# zerocam2S_revE.net
KiCad netlist of a schematic drawn in EAGLE
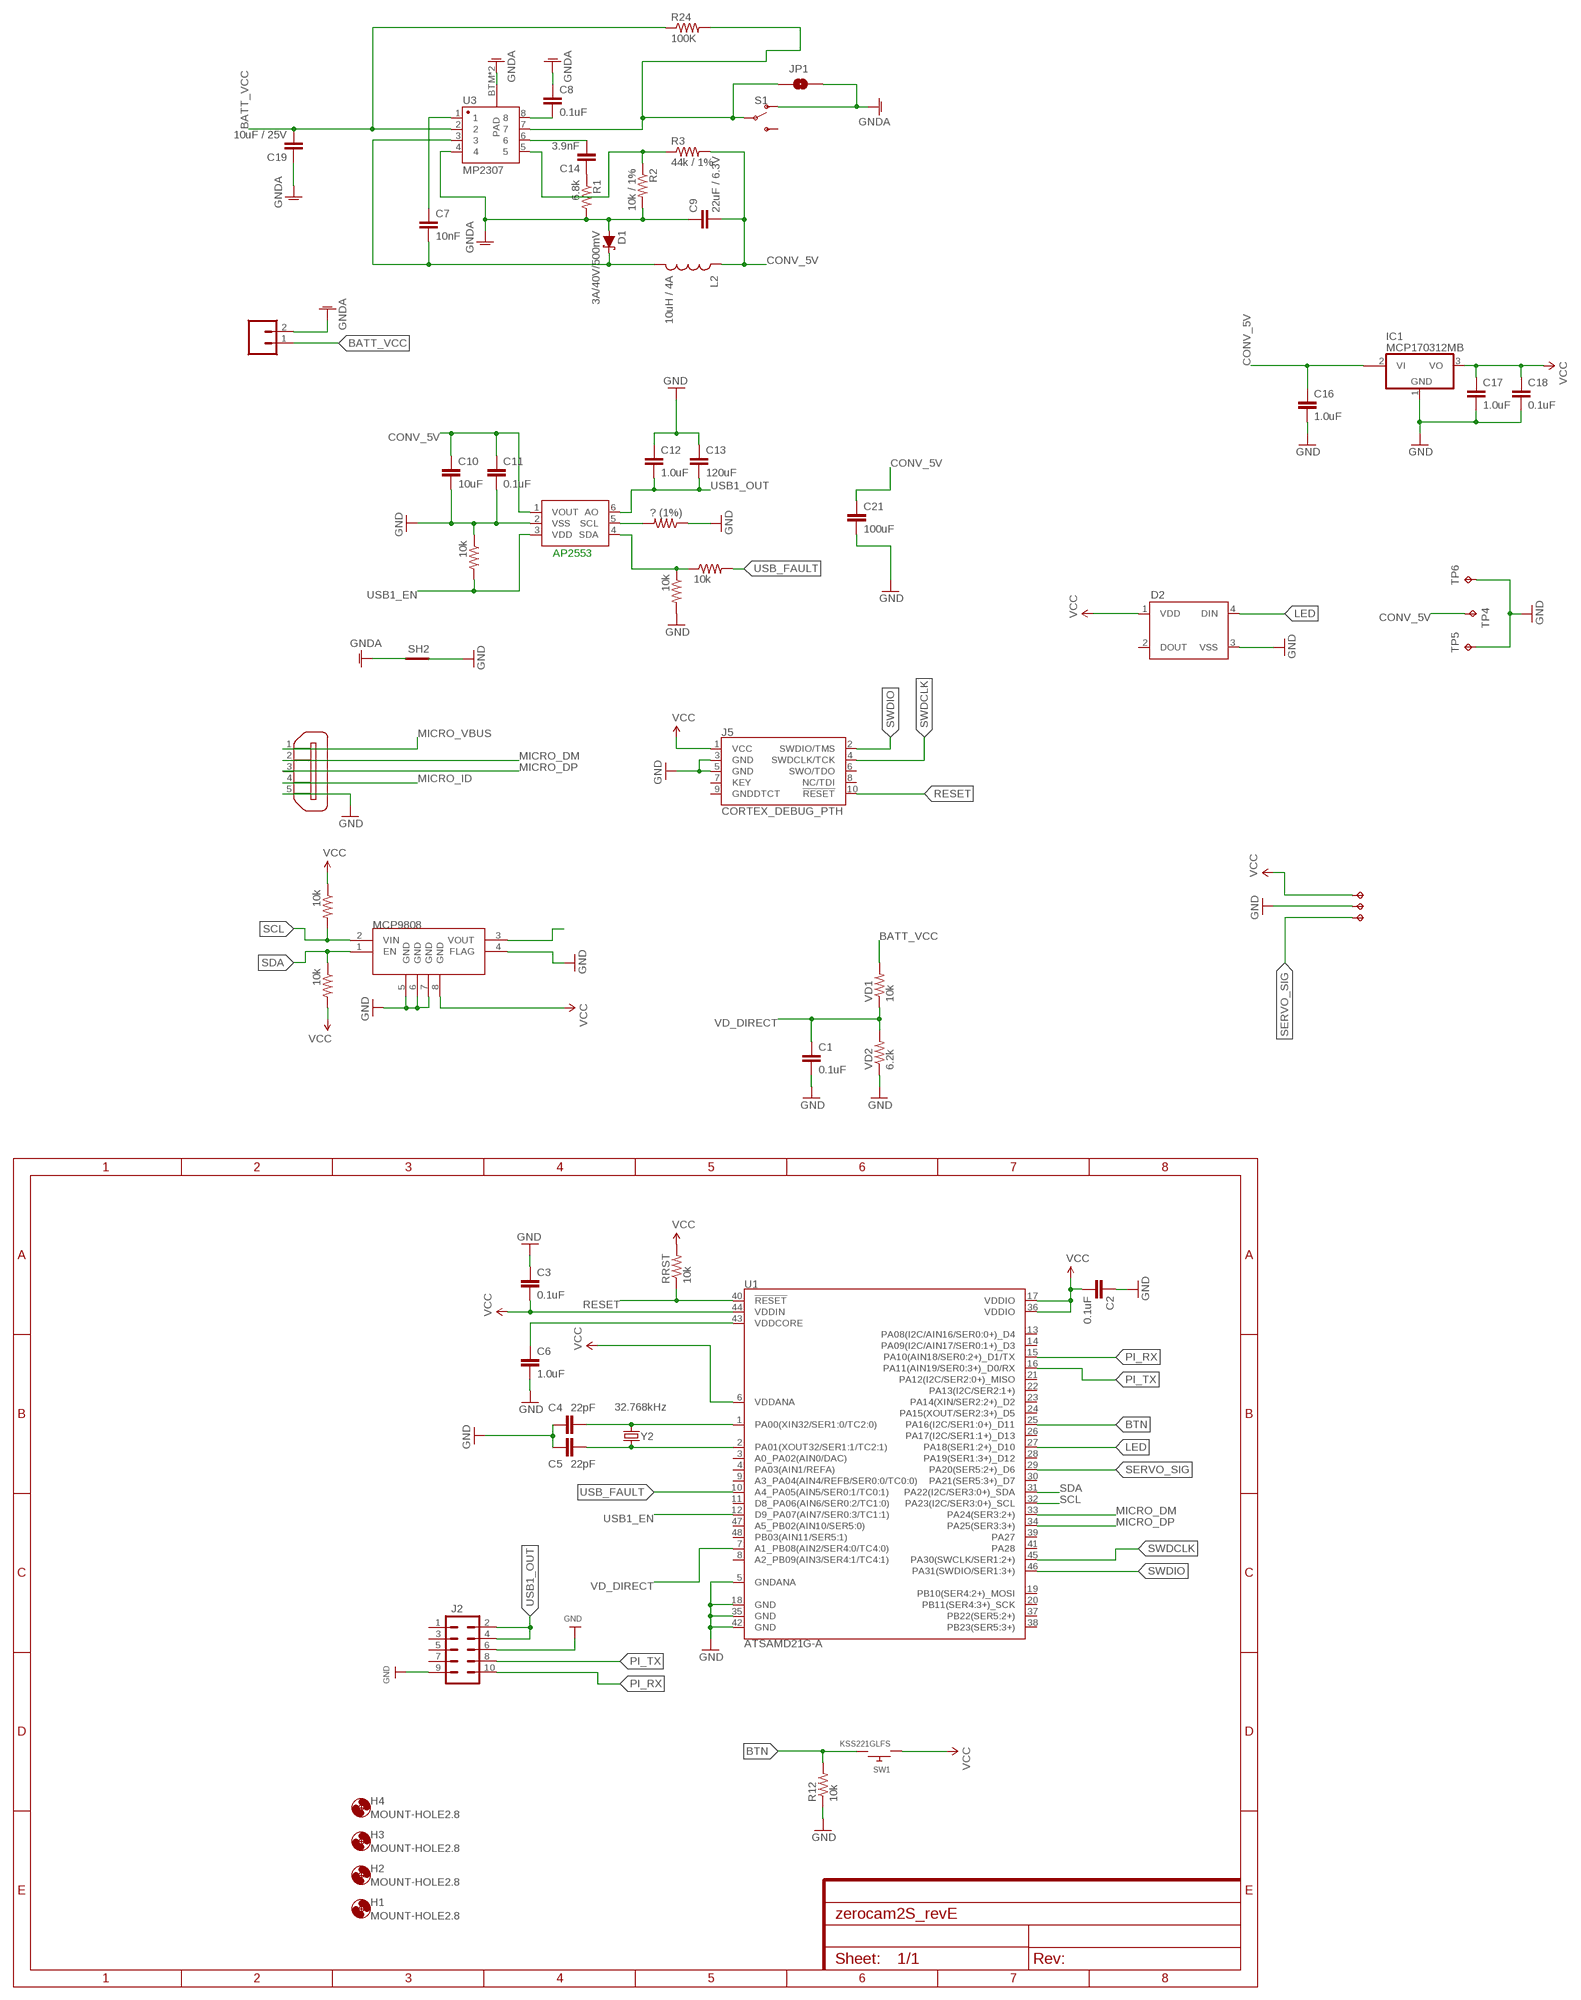
[diagram p0: schematic, sheet 1]

(export (version "E")
  (design (tool "Eeschema 10.0.6"))
  (components
    (comp (ref "AP2553")
      (value "MCP4725")
      (footprint "eagle-import:SOT23-6")
      (libsource (lib "eagle-import") (part "MCP4725SOT-23"))
    )
    (comp (ref "C1")
      (value "0.1uF")
      (footprint "eagle-import:0805")
      (libsource (lib "eagle-import") (part "CAP0805"))
    )
    (comp (ref "C2")
      (value "0.1uF")
      (footprint "eagle-import:0805")
      (libsource (lib "eagle-import") (part "1.0UF-0805-25V-10%"))
    )
    (comp (ref "C3")
      (value "0.1uF")
      (footprint "eagle-import:0805")
      (libsource (lib "eagle-import") (part "1.0UF-0805-25V-10%"))
    )
    (comp (ref "C4")
      (value "22pF")
      (footprint "eagle-import:0805")
      (libsource (lib "eagle-import") (part "SparkFun-Passives_CAP0805"))
    )
    (comp (ref "C5")
      (value "22pF")
      (footprint "eagle-import:0805")
      (libsource (lib "eagle-import") (part "SparkFun-Passives_CAP0805"))
    )
    (comp (ref "C6")
      (value "1.0uF")
      (footprint "eagle-import:0805")
      (libsource (lib "eagle-import") (part "1.0UF-0805-25V-10%"))
    )
    (comp (ref "C7")
      (value "10nF")
      (footprint "eagle-import:0805")
      (libsource (lib "eagle-import") (part "CAP0805"))
    )
    (comp (ref "C8")
      (value "0.1uF")
      (footprint "eagle-import:1206")
      (libsource (lib "eagle-import") (part "CAP1206"))
    )
    (comp (ref "C9")
      (value "22uF / 6.3V")
      (footprint "eagle-import:1210")
      (libsource (lib "eagle-import") (part "CAP1210"))
    )
    (comp (ref "C10")
      (value "10uF")
      (footprint "eagle-import:0805")
      (libsource (lib "eagle-import") (part "1.0UF-0805-25V-10%"))
    )
    (comp (ref "C11")
      (value "0.1uF")
      (footprint "eagle-import:0805")
      (libsource (lib "eagle-import") (part "1.0UF-0805-25V-10%"))
    )
    (comp (ref "C12")
      (value "1.0uF")
      (footprint "eagle-import:1206")
      (libsource (lib "eagle-import") (part "1.0UF-1206-50V-10%"))
    )
    (comp (ref "C13")
      (value "120uF")
      (footprint "eagle-import:1206")
      (libsource (lib "eagle-import") (part "1.0UF-1206-50V-10%"))
    )
    (comp (ref "C14")
      (value "3.9nF")
      (footprint "eagle-import:1206")
      (libsource (lib "eagle-import") (part "CAP1206"))
    )
    (comp (ref "C16")
      (value "1.0uF")
      (footprint "eagle-import:0805")
      (libsource (lib "eagle-import") (part "1.0UF-0805-25V-10%"))
    )
    (comp (ref "C17")
      (value "1.0uF")
      (footprint "eagle-import:1206")
      (libsource (lib "eagle-import") (part "1.0UF-1206-50V-10%"))
    )
    (comp (ref "C18")
      (value "0.1uF")
      (footprint "eagle-import:0805")
      (libsource (lib "eagle-import") (part "1.0UF-0805-25V-10%"))
    )
    (comp (ref "C19")
      (value "10uF / 25V")
      (footprint "eagle-import:1210")
      (libsource (lib "eagle-import") (part "CAP1210"))
    )
    (comp (ref "C21")
      (value "100uF")
      (footprint "eagle-import:1210")
      (libsource (lib "eagle-import") (part "10UF-1210-50V-20%"))
    )
    (comp (ref "D1")
      (value "3A/40V/500mV")
      (footprint "eagle-import:SMA-DIODE")
      (libsource (lib "eagle-import") (part "DIODE-SCHOTTKY-B340A"))
    )
    (comp (ref "D2")
      (value "WS2812B")
      (footprint "eagle-import:WS2812B")
      (libsource (lib "eagle-import") (part "WS2812B"))
    )
    (comp (ref "H1")
      (value "MOUNT-HOLE2.8")
      (footprint "eagle-import:2,8")
      (libsource (lib "eagle-import") (part "MOUNT-HOLE2.8"))
    )
    (comp (ref "H2")
      (value "MOUNT-HOLE2.8")
      (footprint "eagle-import:2,8")
      (libsource (lib "eagle-import") (part "MOUNT-HOLE2.8"))
    )
    (comp (ref "H3")
      (value "MOUNT-HOLE2.8")
      (footprint "eagle-import:2,8")
      (libsource (lib "eagle-import") (part "MOUNT-HOLE2.8"))
    )
    (comp (ref "H4")
      (value "MOUNT-HOLE2.8")
      (footprint "eagle-import:2,8")
      (libsource (lib "eagle-import") (part "MOUNT-HOLE2.8"))
    )
    (comp (ref "IC1")
      (value "MCP170312MB")
      (footprint "eagle-import:SOT89")
      (libsource (lib "eagle-import") (part "MCP1703MB12"))
    )
    (comp (ref "J1")
      (value "CONN_023.5MM-NO_SILK")
      (footprint "eagle-import:SCREWTERMINAL-3.5MM-2-NS")
      (libsource (lib "eagle-import") (part "CONN_023.5MM-NO_SILK"))
    )
    (comp (ref "J2")
      (value "M05X2PTH")
      (footprint "eagle-import:AVR_ICSP")
      (libsource (lib "eagle-import") (part "M05X2PTH"))
    )
    (comp (ref "J5")
      (value "CORTEX_DEBUG_PTH")
      (footprint "eagle-import:2X5-PTH-1.27MM")
      (libsource (lib "eagle-import") (part "CORTEX_DEBUG_PTH"))
    )
    (comp (ref "JP1")
      (value "JUMPER-SMT_2_NO_NO-SILK")
      (footprint "eagle-import:SMT-JUMPER_2_NO_NO-SILK")
      (libsource (lib "eagle-import") (part "JUMPER-SMT_2_NO_NO-SILK"))
    )
    (comp (ref "L2")
      (value "10uH / 4A")
      (footprint "eagle-import:SRU1038")
      (libsource (lib "eagle-import") (part "INDUCTORSRU1038"))
    )
    (comp (ref "MCP9808")
      (value "V_REG_MIC5216")
      (footprint "eagle-import:MSOP8")
      (libsource (lib "eagle-import") (part "V_REG_MIC5216"))
    )
    (comp (ref "R1")
      (value "6.8k")
      (footprint "eagle-import:1206")
      (libsource (lib "eagle-import") (part "SparkFun-Resistors_RESISTOR1206"))
    )
    (comp (ref "R2")
      (value "10k / 1%")
      (footprint "eagle-import:1206")
      (libsource (lib "eagle-import") (part "SparkFun-Resistors_RESISTOR1206"))
    )
    (comp (ref "R3")
      (value "44k / 1%")
      (footprint "eagle-import:1206")
      (libsource (lib "eagle-import") (part "SparkFun-Resistors_RESISTOR1206"))
    )
    (comp (ref "R12")
      (value "10k")
      (footprint "eagle-import:0805")
      (libsource (lib "eagle-import") (part "RESISTOR0805-RES"))
    )
    (comp (ref "R24")
      (value "100K")
      (footprint "eagle-import:1206")
      (libsource (lib "eagle-import") (part "SparkFun-Resistors_RESISTOR1206"))
    )
    (comp (ref "RRST")
      (value "10k")
      (footprint "eagle-import:0805")
      (libsource (lib "eagle-import") (part "RESISTOR0805-RES"))
    )
    (comp (ref "R_I2C_1")
      (value "10k")
      (footprint "eagle-import:0805")
      (libsource (lib "eagle-import") (part "RESISTOR0805-RES"))
    )
    (comp (ref "R_I2C_2")
      (value "10k")
      (footprint "eagle-import:0805")
      (libsource (lib "eagle-import") (part "RESISTOR0805-RES"))
    )
    (comp (ref "R_MOSFET_USB1")
      (value "? (1%)")
      (footprint "eagle-import:0805")
      (libsource (lib "eagle-import") (part "RESISTOR0805-RES"))
    )
    (comp (ref "R_MOSFET_USB2")
      (value "10k")
      (footprint "eagle-import:0805")
      (libsource (lib "eagle-import") (part "RESISTOR0805-RES"))
    )
    (comp (ref "R_MOSFET_USB3")
      (value "10k")
      (footprint "eagle-import:0805")
      (libsource (lib "eagle-import") (part "RESISTOR0805-RES"))
    )
    (comp (ref "R_MOSFET_USB4")
      (value "10k")
      (footprint "eagle-import:0805")
      (libsource (lib "eagle-import") (part "RESISTOR0805-RES"))
    )
    (comp (ref "S1")
      (value "SWITCH-SPDT-SMD-RIGHT-ANGLE")
      (footprint "eagle-import:SWITCH_SPST_SMD_A")
      (libsource (lib "eagle-import") (part "SWITCH-SPDT-SMD-RIGHT-ANGLE"))
    )
    (comp (ref "SH2")
      (value "SHORT-HT5")
      (footprint "eagle-import:SHORT_TOP-50")
      (libsource (lib "eagle-import") (part "SHORT-HT5"))
    )
    (comp (ref "SW1")
      (value "KSS221GLFS")
      (footprint "eagle-import:BTN_CK_KSS")
      (libsource (lib "eagle-import") (part "SWITCH_PUSHBUTTONC&K_KSS"))
    )
    (comp (ref "TP1")
      (value "TPPAD1-13Y")
      (footprint "eagle-import:P1-13Y")
      (libsource (lib "eagle-import") (part "TPPAD1-13Y"))
    )
    (comp (ref "TP2")
      (value "TPPAD1-13Y")
      (footprint "eagle-import:P1-13Y")
      (libsource (lib "eagle-import") (part "TPPAD1-13Y"))
    )
    (comp (ref "TP3")
      (value "TPPAD1-13Y")
      (footprint "eagle-import:P1-13Y")
      (libsource (lib "eagle-import") (part "TPPAD1-13Y"))
    )
    (comp (ref "TP4")
      (value "TPB2,54")
      (footprint "eagle-import:B2,54")
      (libsource (lib "eagle-import") (part "TPB2,54"))
    )
    (comp (ref "TP5")
      (value "TPB2,54")
      (footprint "eagle-import:B2,54")
      (libsource (lib "eagle-import") (part "TPB2,54"))
    )
    (comp (ref "TP6")
      (value "TPB2,54")
      (footprint "eagle-import:B2,54")
      (libsource (lib "eagle-import") (part "TPB2,54"))
    )
    (comp (ref "U1")
      (value "ATSAMD21G-A")
      (footprint "eagle-import:TQFP-48")
      (libsource (lib "eagle-import") (part "ATSAMD21G-A"))
    )
    (comp (ref "U3")
      (value "MP2307")
      (footprint "eagle-import:SO08")
      (libsource (lib "eagle-import") (part "GENERIC-SOIC8MSGEQ7N-FILTER"))
    )
    (comp (ref "VD1")
      (value "10k")
      (footprint "eagle-import:0805")
      (libsource (lib "eagle-import") (part "RESISTOR0805-RES"))
    )
    (comp (ref "VD2")
      (value "6.2k")
      (footprint "eagle-import:0805")
      (libsource (lib "eagle-import") (part "RESISTOR0805-RES"))
    )
    (comp (ref "X2")
      (value "ZX62D-B-5PA8")
      (footprint "eagle-import:ZX62D-B-5PA8")
      (fields (field (name "MF") "Hirose"))
      (libsource (lib "eagle-import") (part "ZX62D-B-5PA8"))
    )
    (comp (ref "Y2")
      (value "32.768kHz")
      (footprint "eagle-import:CRYSTAL-SMD-3.2X1.5MM")
      (libsource (lib "eagle-import") (part "CRYSTAL3.2X1.5MM"))
    )
  )
  (nets
    (net (code "1") (name "/CONV_5V") (class "Default")
      (node (ref "AP2553") (pin "1") (pinfunction "VOUT_1") (pintype "bidirectional"))
      (node (ref "C10") (pin "1") (pinfunction "1_1") (pintype "passive"))
      (node (ref "C11") (pin "1") (pinfunction "1_1") (pintype "passive"))
      (node (ref "C16") (pin "1") (pinfunction "1_1") (pintype "passive"))
      (node (ref "C21") (pin "1") (pinfunction "1_1") (pintype "passive"))
      (node (ref "C9") (pin "2") (pinfunction "2_2") (pintype "passive"))
      (node (ref "IC1") (pin "2@1") (pinfunction "VI1_2@1") (pintype "input"))
      (node (ref "L2") (pin "1") (pinfunction "1_1") (pintype "passive"))
      (node (ref "R3") (pin "2") (pinfunction "2_2") (pintype "passive"))
      (node (ref "TP4") (pin "TP") (pinfunction "TP_TP") (pintype "input"))
    )
    (net (code "2") (name "/MICRO_DM") (class "Default")
      (node (ref "U1") (pin "33") (pinfunction "PA24(SER3:2+)_33") (pintype "bidirectional"))
      (node (ref "X2") (pin "2") (pinfunction "2_2") (pintype "passive"))
    )
    (net (code "3") (name "/MICRO_DP") (class "Default")
      (node (ref "U1") (pin "34") (pinfunction "PA25(SER3:3+)_34") (pintype "bidirectional"))
      (node (ref "X2") (pin "3") (pinfunction "3_3") (pintype "passive"))
    )
    (net (code "4") (name "/MICRO_ID") (class "Default")
      (node (ref "X2") (pin "4") (pinfunction "4_4") (pintype "passive"))
    )
    (net (code "5") (name "/MICRO_VBUS") (class "Default")
      (node (ref "X2") (pin "1") (pinfunction "1_1") (pintype "passive"))
    )
    (net (code "6") (name "/USB1_EN") (class "Default")
      (node (ref "AP2553") (pin "3") (pinfunction "VDD_3") (pintype "bidirectional"))
      (node (ref "R_MOSFET_USB3") (pin "2") (pinfunction "2_2") (pintype "passive"))
      (node (ref "U1") (pin "12") (pinfunction "D9_PA07(AIN7/SER0:3/TC1:1)_12") (pintype "bidirectional"))
    )
    (net (code "7") (name "/VD_DIRECT") (class "Default")
      (node (ref "C1") (pin "1") (pinfunction "1_1") (pintype "passive"))
      (node (ref "U1") (pin "7") (pinfunction "A1_PB08(AIN2/SER4:0/TC4:0)_7") (pintype "bidirectional"))
      (node (ref "VD1") (pin "1") (pinfunction "1_1") (pintype "passive"))
      (node (ref "VD2") (pin "2") (pinfunction "2_2") (pintype "passive"))
    )
    (net (code "8") (name "BATT_VCC") (class "Default")
      (node (ref "C19") (pin "2") (pinfunction "2_2") (pintype "passive"))
      (node (ref "J1") (pin "1") (pinfunction "1_1") (pintype "passive"))
      (node (ref "R24") (pin "1") (pinfunction "1_1") (pintype "passive"))
      (node (ref "U3") (pin "2") (pinfunction "2_2") (pintype "bidirectional"))
      (node (ref "VD1") (pin "2") (pinfunction "2_2") (pintype "passive"))
    )
    (net (code "9") (name "BTN") (class "Default")
      (node (ref "R12") (pin "2") (pinfunction "2_2") (pintype "passive"))
      (node (ref "SW1") (pin "P$2") (pinfunction "P$2_P$2") (pintype "passive"))
      (node (ref "U1") (pin "25") (pinfunction "PA16(I2C/SER1:0+)_D11_25") (pintype "bidirectional"))
    )
    (net (code "10") (name "GND") (class "Default")
      (node (ref "AP2553") (pin "2") (pinfunction "VSS_2") (pintype "bidirectional"))
      (node (ref "C1") (pin "2") (pinfunction "2_2") (pintype "passive"))
      (node (ref "C10") (pin "2") (pinfunction "2_2") (pintype "passive"))
      (node (ref "C11") (pin "2") (pinfunction "2_2") (pintype "passive"))
      (node (ref "C12") (pin "1") (pinfunction "1_1") (pintype "passive"))
      (node (ref "C13") (pin "1") (pinfunction "1_1") (pintype "passive"))
      (node (ref "C16") (pin "2") (pinfunction "2_2") (pintype "passive"))
      (node (ref "C17") (pin "2") (pinfunction "2_2") (pintype "passive"))
      (node (ref "C18") (pin "2") (pinfunction "2_2") (pintype "passive"))
      (node (ref "C2") (pin "1") (pinfunction "1_1") (pintype "passive"))
      (node (ref "C21") (pin "2") (pinfunction "2_2") (pintype "passive"))
      (node (ref "C3") (pin "1") (pinfunction "1_1") (pintype "passive"))
      (node (ref "C4") (pin "1") (pinfunction "1_1") (pintype "passive"))
      (node (ref "C5") (pin "1") (pinfunction "1_1") (pintype "passive"))
      (node (ref "C6") (pin "2") (pinfunction "2_2") (pintype "passive"))
      (node (ref "D2") (pin "3") (pinfunction "VSS_3") (pintype "power_in"))
      (node (ref "IC1") (pin "1") (pinfunction "GND_1") (pintype "passive"))
      (node (ref "J2") (pin "6") (pinfunction "6_6") (pintype "passive"))
      (node (ref "J2") (pin "9") (pinfunction "9_9") (pintype "passive"))
      (node (ref "J5") (pin "3") (pinfunction "GND_3") (pintype "bidirectional"))
      (node (ref "J5") (pin "5") (pinfunction "GND_5") (pintype "bidirectional"))
      (node (ref "MCP9808") (pin "4") (pinfunction "FLAG_4") (pintype "bidirectional"))
      (node (ref "MCP9808") (pin "5") (pinfunction "GND_5") (pintype "bidirectional"))
      (node (ref "MCP9808") (pin "6") (pinfunction "GND_6") (pintype "bidirectional"))
      (node (ref "MCP9808") (pin "7") (pinfunction "GND_7") (pintype "bidirectional"))
      (node (ref "R12") (pin "1") (pinfunction "1_1") (pintype "passive"))
      (node (ref "R_MOSFET_USB1") (pin "1") (pinfunction "1_1") (pintype "passive"))
      (node (ref "R_MOSFET_USB2") (pin "2") (pinfunction "2_2") (pintype "passive"))
      (node (ref "R_MOSFET_USB3") (pin "1") (pinfunction "1_1") (pintype "passive"))
      (node (ref "SH2") (pin "2") (pinfunction "P$2_2") (pintype "bidirectional"))
      (node (ref "TP2") (pin "TP") (pinfunction "TP_TP") (pintype "input"))
      (node (ref "TP5") (pin "TP") (pinfunction "TP_TP") (pintype "input"))
      (node (ref "TP6") (pin "TP") (pinfunction "TP_TP") (pintype "input"))
      (node (ref "U1") (pin "18") (pinfunction "GND_18") (pintype "bidirectional"))
      (node (ref "U1") (pin "35") (pinfunction "GND_35") (pintype "bidirectional"))
      (node (ref "U1") (pin "42") (pinfunction "GND_42") (pintype "bidirectional"))
      (node (ref "U1") (pin "5") (pinfunction "GNDANA_5") (pintype "bidirectional"))
      (node (ref "VD2") (pin "1") (pinfunction "1_1") (pintype "passive"))
      (node (ref "X2") (pin "5") (pinfunction "5_5") (pintype "passive"))
    )
    (net (code "11") (name "GNDA") (class "Default")
      (node (ref "C19") (pin "1") (pinfunction "1_1") (pintype "passive"))
      (node (ref "C8") (pin "1") (pinfunction "1_1") (pintype "passive"))
      (node (ref "C9") (pin "1") (pinfunction "1_1") (pintype "passive"))
      (node (ref "D1") (pin "A") (pinfunction "A_A") (pintype "passive"))
      (node (ref "J1") (pin "2") (pinfunction "2_2") (pintype "passive"))
      (node (ref "JP1") (pin "2") (pinfunction "2_2") (pintype "passive"))
      (node (ref "R1") (pin "2") (pinfunction "2_2") (pintype "passive"))
      (node (ref "R2") (pin "2") (pinfunction "2_2") (pintype "passive"))
      (node (ref "S1") (pin "1") (pinfunction "O_1") (pintype "passive"))
      (node (ref "SH2") (pin "1") (pinfunction "P$1_1") (pintype "bidirectional"))
      (node (ref "U3") (pin "4") (pinfunction "4_4") (pintype "bidirectional"))
      (node (ref "U3") (pin "BTM") (pinfunction "PAD_BTM") (pintype "bidirectional"))
      (node (ref "U3") (pin "P$1") (pinfunction "PAD_P$1") (pintype "bidirectional"))
    )
    (net (code "12") (name "LED") (class "Default")
      (node (ref "D2") (pin "4") (pinfunction "DIN_4") (pintype "input"))
      (node (ref "U1") (pin "27") (pinfunction "PA18(SER1:2+)_D10_27") (pintype "bidirectional"))
    )
    (net (code "13") (name "Net-(AP2553-SCL)") (class "Default")
      (node (ref "AP2553") (pin "5") (pinfunction "SCL_5") (pintype "bidirectional"))
      (node (ref "R_MOSFET_USB1") (pin "2") (pinfunction "2_2") (pintype "passive"))
    )
    (net (code "14") (name "Net-(AP2553-SDA)") (class "Default")
      (node (ref "AP2553") (pin "4") (pinfunction "SDA_4") (pintype "bidirectional"))
      (node (ref "R_MOSFET_USB2") (pin "1") (pinfunction "1_1") (pintype "passive"))
      (node (ref "R_MOSFET_USB4") (pin "1") (pinfunction "1_1") (pintype "passive"))
    )
    (net (code "15") (name "Net-(C7-Pad1)") (class "Default")
      (node (ref "C7") (pin "1") (pinfunction "1_1") (pintype "passive"))
      (node (ref "U3") (pin "1") (pinfunction "1_1") (pintype "bidirectional"))
    )
    (net (code "16") (name "Net-(C7-Pad2)") (class "Default")
      (node (ref "C7") (pin "2") (pinfunction "2_2") (pintype "passive"))
      (node (ref "D1") (pin "C") (pinfunction "C_C") (pintype "passive"))
      (node (ref "L2") (pin "2") (pinfunction "2_2") (pintype "passive"))
      (node (ref "U3") (pin "3") (pinfunction "3_3") (pintype "bidirectional"))
    )
    (net (code "17") (name "Net-(C8-Pad2)") (class "Default")
      (node (ref "C8") (pin "2") (pinfunction "2_2") (pintype "passive"))
      (node (ref "U3") (pin "8") (pinfunction "8_8") (pintype "bidirectional"))
    )
    (net (code "18") (name "Net-(C14-Pad1)") (class "Default")
      (node (ref "C14") (pin "1") (pinfunction "1_1") (pintype "passive"))
      (node (ref "R1") (pin "1") (pinfunction "1_1") (pintype "passive"))
    )
    (net (code "19") (name "Net-(C14-Pad2)") (class "Default")
      (node (ref "C14") (pin "2") (pinfunction "2_2") (pintype "passive"))
      (node (ref "U3") (pin "6") (pinfunction "6_6") (pintype "bidirectional"))
    )
    (net (code "20") (name "Net-(R2-Pad1)") (class "Default")
      (node (ref "R2") (pin "1") (pinfunction "1_1") (pintype "passive"))
      (node (ref "R3") (pin "1") (pinfunction "1_1") (pintype "passive"))
      (node (ref "U3") (pin "5") (pinfunction "5_5") (pintype "bidirectional"))
    )
    (net (code "21") (name "Net-(S1-P)") (class "Default")
      (node (ref "JP1") (pin "1") (pinfunction "1_1") (pintype "passive"))
      (node (ref "R24") (pin "2") (pinfunction "2_2") (pintype "passive"))
      (node (ref "S1") (pin "2") (pinfunction "P_2") (pintype "passive"))
      (node (ref "U3") (pin "7") (pinfunction "7_7") (pintype "bidirectional"))
    )
    (net (code "22") (name "Net-(U1-PA00(XIN32{slash}SER1:0{slash}TC2:0))") (class "Default")
      (node (ref "C4") (pin "2") (pinfunction "2_2") (pintype "passive"))
      (node (ref "U1") (pin "1") (pinfunction "PA00(XIN32/SER1:0/TC2:0)_1") (pintype "bidirectional"))
      (node (ref "Y2") (pin "P$2") (pinfunction "2_P$2") (pintype "passive"))
    )
    (net (code "23") (name "Net-(U1-PA01(XOUT32{slash}SER1:1{slash}TC2:1))") (class "Default")
      (node (ref "C5") (pin "2") (pinfunction "2_2") (pintype "passive"))
      (node (ref "U1") (pin "2") (pinfunction "PA01(XOUT32/SER1:1/TC2:1)_2") (pintype "bidirectional"))
      (node (ref "Y2") (pin "P$1") (pinfunction "1_P$1") (pintype "passive"))
    )
    (net (code "24") (name "Net-(U1-VDDCORE)") (class "Default")
      (node (ref "C6") (pin "1") (pinfunction "1_1") (pintype "passive"))
      (node (ref "U1") (pin "43") (pinfunction "VDDCORE_43") (pintype "bidirectional"))
    )
    (net (code "25") (name "PI_RX") (class "Default")
      (node (ref "J2") (pin "10") (pinfunction "10_10") (pintype "passive"))
      (node (ref "U1") (pin "15") (pinfunction "PA10(AIN18/SER0:2+)_D1/TX_15") (pintype "bidirectional"))
    )
    (net (code "26") (name "PI_TX") (class "Default")
      (node (ref "J2") (pin "8") (pinfunction "8_8") (pintype "passive"))
      (node (ref "U1") (pin "16") (pinfunction "PA11(AIN19/SER0:3+)_D0/RX_16") (pintype "bidirectional"))
    )
    (net (code "27") (name "RESET") (class "Default")
      (node (ref "J5") (pin "10") (pinfunction "~{RESET}_10") (pintype "bidirectional"))
      (node (ref "RRST") (pin "1") (pinfunction "1_1") (pintype "passive"))
      (node (ref "U1") (pin "40") (pinfunction "~{RESET}_40") (pintype "bidirectional"))
    )
    (net (code "28") (name "SCL") (class "Default")
      (node (ref "MCP9808") (pin "2") (pinfunction "VIN_2") (pintype "bidirectional"))
      (node (ref "R_I2C_1") (pin "2") (pinfunction "2_2") (pintype "passive"))
      (node (ref "U1") (pin "32") (pinfunction "PA23(I2C/SER3:0+)_SCL_32") (pintype "bidirectional"))
    )
    (net (code "29") (name "SDA") (class "Default")
      (node (ref "MCP9808") (pin "1") (pinfunction "EN_1") (pintype "bidirectional"))
      (node (ref "R_I2C_2") (pin "1") (pinfunction "1_1") (pintype "passive"))
      (node (ref "U1") (pin "31") (pinfunction "PA22(I2C/SER3:0+)_SDA_31") (pintype "bidirectional"))
    )
    (net (code "30") (name "SERVO_SIG") (class "Default")
      (node (ref "TP3") (pin "TP") (pinfunction "TP_TP") (pintype "input"))
      (node (ref "U1") (pin "29") (pinfunction "PA20(SER5:2+)_D6_29") (pintype "bidirectional"))
    )
    (net (code "31") (name "SWDCLK") (class "Default")
      (node (ref "J5") (pin "4") (pinfunction "SWDCLK/TCK_4") (pintype "bidirectional"))
      (node (ref "U1") (pin "45") (pinfunction "PA30(SWCLK/SER1:2+)_45") (pintype "bidirectional"))
    )
    (net (code "32") (name "SWDIO") (class "Default")
      (node (ref "J5") (pin "2") (pinfunction "SWDIO/TMS_2") (pintype "bidirectional"))
      (node (ref "U1") (pin "46") (pinfunction "PA31(SWDIO/SER1:3+)_46") (pintype "bidirectional"))
    )
    (net (code "33") (name "USB1_OUT") (class "Default")
      (node (ref "AP2553") (pin "6") (pinfunction "AO_6") (pintype "bidirectional"))
      (node (ref "C12") (pin "2") (pinfunction "2_2") (pintype "passive"))
      (node (ref "C13") (pin "2") (pinfunction "2_2") (pintype "passive"))
      (node (ref "J2") (pin "2") (pinfunction "2_2") (pintype "passive"))
      (node (ref "J2") (pin "4") (pinfunction "4_4") (pintype "passive"))
    )
    (net (code "34") (name "USB_FAULT") (class "Default")
      (node (ref "R_MOSFET_USB4") (pin "2") (pinfunction "2_2") (pintype "passive"))
      (node (ref "U1") (pin "10") (pinfunction "A4_PA05(AIN5/SER0:1/TC0:1)_10") (pintype "bidirectional"))
    )
    (net (code "35") (name "VCC") (class "Default")
      (node (ref "C17") (pin "1") (pinfunction "1_1") (pintype "passive"))
      (node (ref "C18") (pin "1") (pinfunction "1_1") (pintype "passive"))
      (node (ref "C2") (pin "2") (pinfunction "2_2") (pintype "passive"))
      (node (ref "C3") (pin "2") (pinfunction "2_2") (pintype "passive"))
      (node (ref "D2") (pin "1") (pinfunction "VDD_1") (pintype "power_in"))
      (node (ref "IC1") (pin "3") (pinfunction "VO_3") (pintype "passive"))
      (node (ref "J5") (pin "1") (pinfunction "VCC_1") (pintype "bidirectional"))
      (node (ref "MCP9808") (pin "8") (pinfunction "GND_8") (pintype "bidirectional"))
      (node (ref "RRST") (pin "2") (pinfunction "2_2") (pintype "passive"))
      (node (ref "R_I2C_1") (pin "1") (pinfunction "1_1") (pintype "passive"))
      (node (ref "R_I2C_2") (pin "2") (pinfunction "2_2") (pintype "passive"))
      (node (ref "SW1") (pin "P$1") (pinfunction "P$1_P$1") (pintype "passive"))
      (node (ref "TP1") (pin "TP") (pinfunction "TP_TP") (pintype "input"))
      (node (ref "U1") (pin "17") (pinfunction "VDDIO_17") (pintype "bidirectional"))
      (node (ref "U1") (pin "36") (pinfunction "VDDIO_36") (pintype "bidirectional"))
      (node (ref "U1") (pin "44") (pinfunction "VDDIN_44") (pintype "bidirectional"))
      (node (ref "U1") (pin "6") (pinfunction "VDDANA_6") (pintype "bidirectional"))
    )
    (net (code "36") (name "unconnected-(D2-DOUT-Pad2)") (class "Default")
      (node (ref "D2") (pin "2") (pinfunction "DOUT_2") (pintype "output"))
    )
    (net (code "37") (name "unconnected-(IC1-VI-Pad2)") (class "Default")
      (node (ref "IC1") (pin "2") (pinfunction "VI_2") (pintype "input"))
    )
    (net (code "38") (name "unconnected-(J2-Pad1)") (class "Default")
      (node (ref "J2") (pin "1") (pinfunction "1_1") (pintype "passive"))
    )
    (net (code "39") (name "unconnected-(J2-Pad3)") (class "Default")
      (node (ref "J2") (pin "3") (pinfunction "3_3") (pintype "passive"))
    )
    (net (code "40") (name "unconnected-(J2-Pad5)") (class "Default")
      (node (ref "J2") (pin "5") (pinfunction "5_5") (pintype "passive"))
    )
    (net (code "41") (name "unconnected-(J2-Pad7)") (class "Default")
      (node (ref "J2") (pin "7") (pinfunction "7_7") (pintype "passive"))
    )
    (net (code "42") (name "unconnected-(J5-GNDDTCT-Pad9)") (class "Default")
      (node (ref "J5") (pin "9") (pinfunction "GNDDTCT_9") (pintype "bidirectional"))
    )
    (net (code "43") (name "unconnected-(J5-KEY-Pad7)") (class "Default")
      (node (ref "J5") (pin "7") (pinfunction "KEY_7") (pintype "bidirectional"))
    )
    (net (code "44") (name "unconnected-(J5-NC{slash}TDI-Pad8)") (class "Default")
      (node (ref "J5") (pin "8") (pinfunction "NC/TDI_8") (pintype "bidirectional"))
    )
    (net (code "45") (name "unconnected-(J5-SWO{slash}TDO-Pad6)") (class "Default")
      (node (ref "J5") (pin "6") (pinfunction "SWO/TDO_6") (pintype "bidirectional"))
    )
    (net (code "46") (name "unconnected-(MCP9808-VOUT-Pad3)") (class "Default")
      (node (ref "MCP9808") (pin "3") (pinfunction "VOUT_3") (pintype "bidirectional"))
    )
    (net (code "47") (name "unconnected-(S1-S-Pad3)") (class "Default")
      (node (ref "S1") (pin "3") (pinfunction "S_3") (pintype "passive"))
    )
    (net (code "48") (name "unconnected-(U1-A0_PA02(AIN0{slash}DAC)-Pad3)") (class "Default")
      (node (ref "U1") (pin "3") (pinfunction "A0_PA02(AIN0/DAC)_3") (pintype "bidirectional"))
    )
    (net (code "49") (name "unconnected-(U1-A2_PB09(AIN3{slash}SER4:1{slash}TC4:1)-Pad8)") (class "Default")
      (node (ref "U1") (pin "8") (pinfunction "A2_PB09(AIN3/SER4:1/TC4:1)_8") (pintype "bidirectional"))
    )
    (net (code "50") (name "unconnected-(U1-A3_PA04(AIN4{slash}REFB{slash}SER0:0{slash}TC0:0)-Pad9)") (class "Default")
      (node (ref "U1") (pin "9") (pinfunction "A3_PA04(AIN4/REFB/SER0:0/TC0:0)_9") (pintype "bidirectional"))
    )
    (net (code "51") (name "unconnected-(U1-A5_PB02(AIN10{slash}SER5:0)-Pad47)") (class "Default")
      (node (ref "U1") (pin "47") (pinfunction "A5_PB02(AIN10/SER5:0)_47") (pintype "bidirectional"))
    )
    (net (code "52") (name "unconnected-(U1-D8_PA06(AIN6{slash}SER0:2{slash}TC1:0)-Pad11)") (class "Default")
      (node (ref "U1") (pin "11") (pinfunction "D8_PA06(AIN6/SER0:2/TC1:0)_11") (pintype "bidirectional"))
    )
    (net (code "53") (name "unconnected-(U1-PA03(AIN1{slash}REFA)-Pad4)") (class "Default")
      (node (ref "U1") (pin "4") (pinfunction "PA03(AIN1/REFA)_4") (pintype "bidirectional"))
    )
    (net (code "54") (name "unconnected-(U1-PA08(I2C{slash}AIN16{slash}SER0:0+)_D4-Pad13)") (class "Default")
      (node (ref "U1") (pin "13") (pinfunction "PA08(I2C/AIN16/SER0:0+)_D4_13") (pintype "bidirectional"))
    )
    (net (code "55") (name "unconnected-(U1-PA09(I2C{slash}AIN17{slash}SER0:1+)_D3-Pad14)") (class "Default")
      (node (ref "U1") (pin "14") (pinfunction "PA09(I2C/AIN17/SER0:1+)_D3_14") (pintype "bidirectional"))
    )
    (net (code "56") (name "unconnected-(U1-PA12(I2C{slash}SER2:0+)_MISO-Pad21)") (class "Default")
      (node (ref "U1") (pin "21") (pinfunction "PA12(I2C/SER2:0+)_MISO_21") (pintype "bidirectional"))
    )
    (net (code "57") (name "unconnected-(U1-PA13(I2C{slash}SER2:1+)-Pad22)") (class "Default")
      (node (ref "U1") (pin "22") (pinfunction "PA13(I2C/SER2:1+)_22") (pintype "bidirectional"))
    )
    (net (code "58") (name "unconnected-(U1-PA14(XIN{slash}SER2:2+)_D2-Pad23)") (class "Default")
      (node (ref "U1") (pin "23") (pinfunction "PA14(XIN/SER2:2+)_D2_23") (pintype "bidirectional"))
    )
    (net (code "59") (name "unconnected-(U1-PA15(XOUT{slash}SER2:3+)_D5-Pad24)") (class "Default")
      (node (ref "U1") (pin "24") (pinfunction "PA15(XOUT/SER2:3+)_D5_24") (pintype "bidirectional"))
    )
    (net (code "60") (name "unconnected-(U1-PA17(I2C{slash}SER1:1+)_D13-Pad26)") (class "Default")
      (node (ref "U1") (pin "26") (pinfunction "PA17(I2C/SER1:1+)_D13_26") (pintype "bidirectional"))
    )
    (net (code "61") (name "unconnected-(U1-PA19(SER1:3+)_D12-Pad28)") (class "Default")
      (node (ref "U1") (pin "28") (pinfunction "PA19(SER1:3+)_D12_28") (pintype "bidirectional"))
    )
    (net (code "62") (name "unconnected-(U1-PA21(SER5:3+)_D7-Pad30)") (class "Default")
      (node (ref "U1") (pin "30") (pinfunction "PA21(SER5:3+)_D7_30") (pintype "bidirectional"))
    )
    (net (code "63") (name "unconnected-(U1-PA27-Pad39)") (class "Default")
      (node (ref "U1") (pin "39") (pinfunction "PA27_39") (pintype "bidirectional"))
    )
    (net (code "64") (name "unconnected-(U1-PA28-Pad41)") (class "Default")
      (node (ref "U1") (pin "41") (pinfunction "PA28_41") (pintype "bidirectional"))
    )
    (net (code "65") (name "unconnected-(U1-PB03(AIN11{slash}SER5:1)-Pad48)") (class "Default")
      (node (ref "U1") (pin "48") (pinfunction "PB03(AIN11/SER5:1)_48") (pintype "bidirectional"))
    )
    (net (code "66") (name "unconnected-(U1-PB10(SER4:2+)_MOSI-Pad19)") (class "Default")
      (node (ref "U1") (pin "19") (pinfunction "PB10(SER4:2+)_MOSI_19") (pintype "bidirectional"))
    )
    (net (code "67") (name "unconnected-(U1-PB11(SER4:3+)_SCK-Pad20)") (class "Default")
      (node (ref "U1") (pin "20") (pinfunction "PB11(SER4:3+)_SCK_20") (pintype "bidirectional"))
    )
    (net (code "68") (name "unconnected-(U1-PB22(SER5:2+)-Pad37)") (class "Default")
      (node (ref "U1") (pin "37") (pinfunction "PB22(SER5:2+)_37") (pintype "bidirectional"))
    )
    (net (code "69") (name "unconnected-(U1-PB23(SER5:3+)-Pad38)") (class "Default")
      (node (ref "U1") (pin "38") (pinfunction "PB23(SER5:3+)_38") (pintype "bidirectional"))
    )
  )
)
